# Power_Sheet.net
KiCad netlist of a schematic drawn in Altium Designer
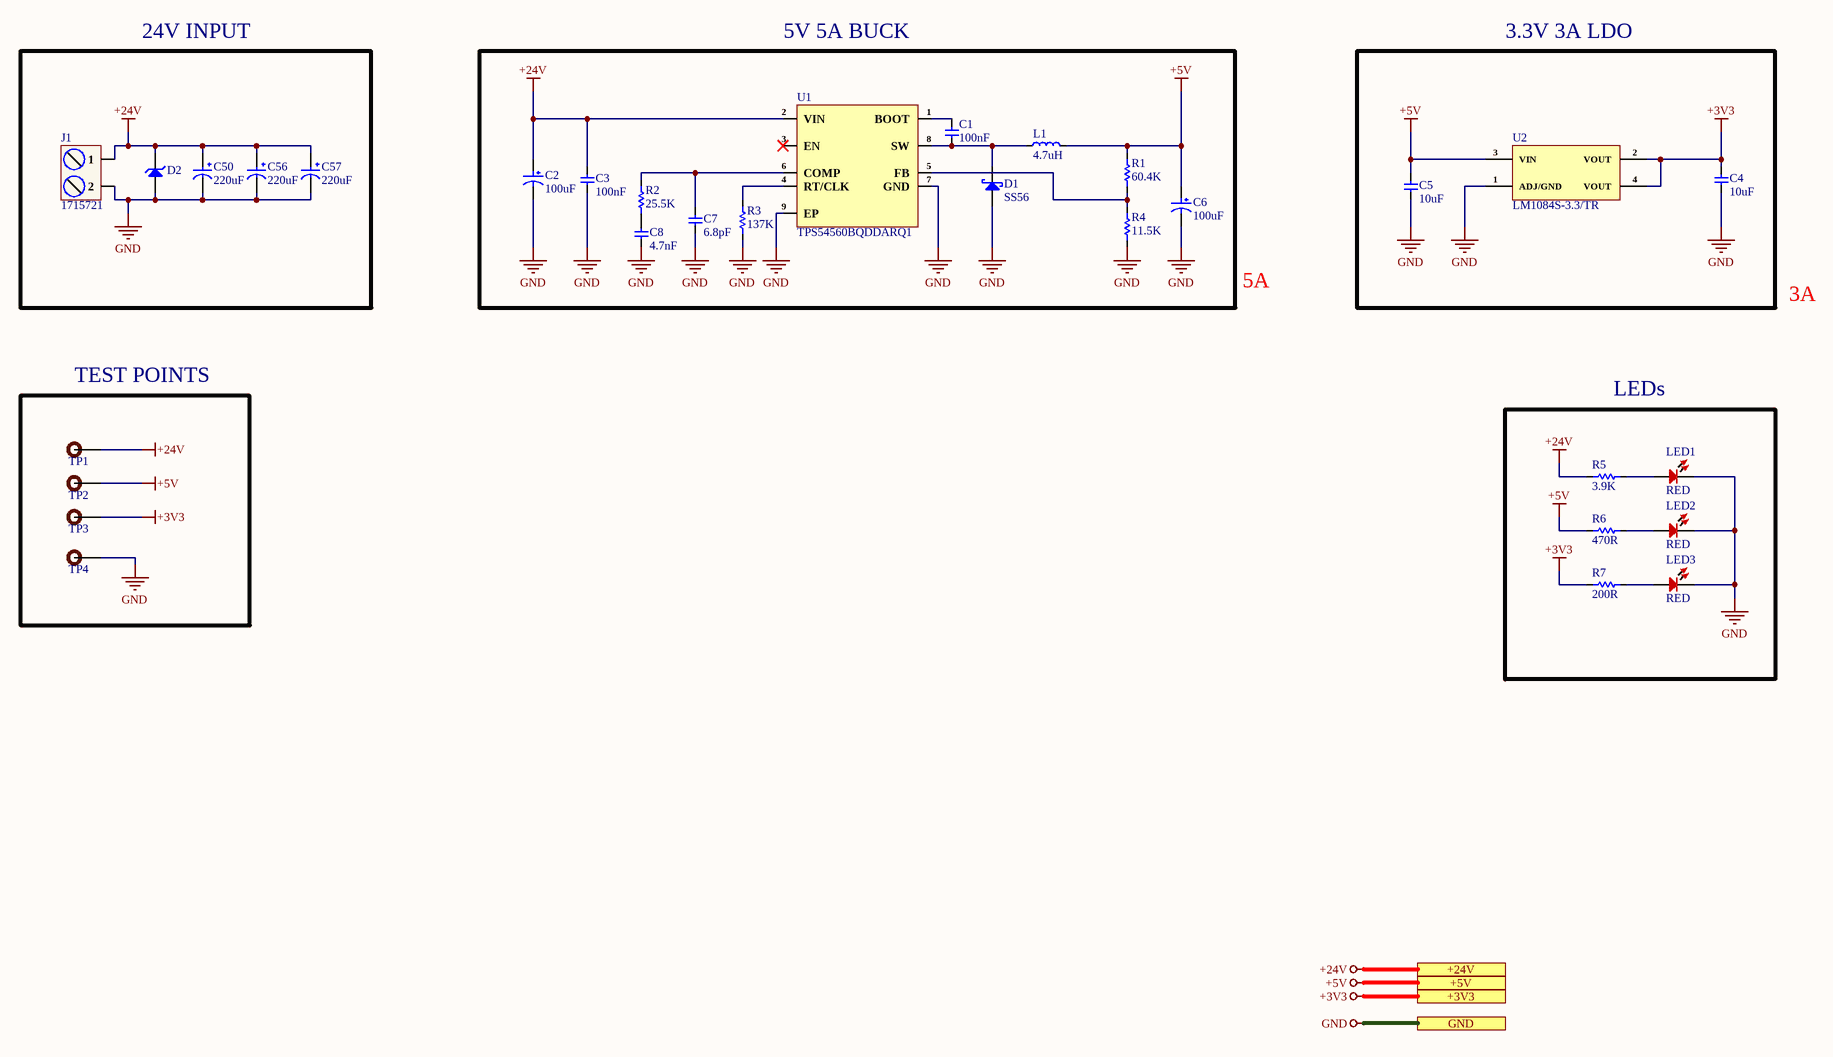
[diagram p0: Power_Sheet.SchDoc]

(export (version "E")
  (design (tool "Eeschema 10.0.6"))
  (components
    (comp (ref "C1")
      (value "100nF")
      (footprint "cap-0402")
      (description "CAP CER 0.1UF 50V X7R 0402")
      (fields
        (field (name "MANUFACTURER") "TDK")
        (field (name "MANUFACTURER PART NUMBER") "C1005X7R1H104KT000F")
      )
      (libsource (lib "eSpark Libraries") (part "C1005X7R1H104KT000F"))
    )
    (comp (ref "C2")
      (value "100uF")
      (footprint "RVT1A101M0605")
      (description "100uF 10V 55mA@120Hz ±20% SMD,D6.3xL5.4mm Aluminum Electrolytic Capacitors - SMD ROHS")
      (fields
        (field (name "MANUFACTURER") "ROQANG")
        (field (name "MANUFACTURER PART NUMBER") "RVT1A101M0605")
      )
      (libsource (lib "eSpark Libraries") (part "RVT1A101M0605"))
    )
    (comp (ref "C3")
      (value "100nF")
      (footprint "cap-0402")
      (description "CAP CER 0.1UF 50V X7R 0402")
      (fields
        (field (name "MANUFACTURER") "TDK")
        (field (name "MANUFACTURER PART NUMBER") "C1005X7R1H104KT000F")
      )
      (libsource (lib "eSpark Libraries") (part "C1005X7R1H104KT000F"))
    )
    (comp (ref "C4")
      (value "10uF")
      (footprint "Cap-0603")
      (description "CAP CER 10UF 25V X5R 0603")
      (fields
        (field (name "MANUFACTURER") "TDK")
        (field (name "MANUFACTURER PART NUMBER") "C1608X5R1E106M080AC")
      )
      (libsource (lib "eSpark Libraries") (part "C1608X5R1E106M080AC"))
    )
    (comp (ref "C5")
      (value "10uF")
      (footprint "Cap-0603")
      (description "CAP CER 10UF 25V X5R 0603")
      (fields
        (field (name "MANUFACTURER") "TDK")
        (field (name "MANUFACTURER PART NUMBER") "C1608X5R1E106M080AC")
      )
      (libsource (lib "eSpark Libraries") (part "C1608X5R1E106M080AC"))
    )
    (comp (ref "C6")
      (value "100uF")
      (footprint "RVT1A101M0605")
      (description "100uF 10V 55mA@120Hz ±20% SMD,D6.3xL5.4mm Aluminum Electrolytic Capacitors - SMD ROHS")
      (fields
        (field (name "MANUFACTURER") "ROQANG")
        (field (name "MANUFACTURER PART NUMBER") "RVT1A101M0605")
      )
      (libsource (lib "eSpark Libraries") (part "RVT1A101M0605"))
    )
    (comp (ref "C7")
      (value "6.8pF")
      (footprint "Cap-0402")
      (description "CAP CER 6.8PF 50V C0G/NPO 0402")
      (fields
        (field (name "MANUFACTURER") "Yageo")
        (field (name "MANUFACTURER PART NUMBER") "CC0402CRNPO9BN6R8")
      )
      (libsource (lib "eSpark Libraries") (part "CC0402CRNPO9BN6R8"))
    )
    (comp (ref "C8")
      (value "4.7nF")
      (footprint "Cap-0402")
      (description "CAP CER 4700PF 50V X7R 0402")
      (fields
        (field (name "MANUFACTURER") "Yageo")
        (field (name "MANUFACTURER PART NUMBER") "CC0402KRX7R9BB472")
      )
      (libsource (lib "eSpark Libraries") (part "CC0402KRX7R9BB472"))
    )
    (comp (ref "C50")
      (value "220uF")
      (footprint "UCD-220uF-10mmDia")
      (description "CAP ALUM 220UF 20% 50V SMD")
      (fields
        (field (name "MANUFACTURER") "Nichicon")
        (field (name "MANUFACTURER PART NUMBER") "UCD1H221MNL1GS")
      )
      (libsource (lib "eSpark Libraries") (part "UCD1H221MNL1GS"))
    )
    (comp (ref "C56")
      (value "220uF")
      (footprint "UCD-220uF-10mmDia")
      (description "CAP ALUM 220UF 20% 50V SMD")
      (fields
        (field (name "MANUFACTURER") "Nichicon")
        (field (name "MANUFACTURER PART NUMBER") "UCD1H221MNL1GS")
      )
      (libsource (lib "eSpark Libraries") (part "UCD1H221MNL1GS"))
    )
    (comp (ref "C57")
      (value "220uF")
      (footprint "UCD-220uF-10mmDia")
      (description "CAP ALUM 220UF 20% 50V SMD")
      (fields
        (field (name "MANUFACTURER") "Nichicon")
        (field (name "MANUFACTURER PART NUMBER") "UCD1H221MNL1GS")
      )
      (libsource (lib "eSpark Libraries") (part "UCD1H221MNL1GS"))
    )
    (comp (ref "D1")
      (value "SS56")
      (footprint "SMA")
      (description "DIODE SCHOTTKY 60V 5A SMA")
      (fields (field (name "MANUFACTURER") "MDD"))
      (libsource (lib "eSpark Libraries") (part "SS56"))
    )
    (comp (ref "D2")
      (value "SMBJ28A-13-F")
      (footprint "SMB_")
      (description "TVS DIODE 28VWM 45.4VC SMB")
      (fields (field (name "MANUFACTURER") "Diodes"))
      (libsource (lib "eSpark Libraries") (part "SMBJ28A-13-F"))
    )
    (comp (ref "J1")
      (value "1715721")
      (footprint "1715721")
      (description "TERM BLK 2P SIDE ENT 5.08MM PCB")
      (fields (field (name "MANUFACTURER") "Phoenix Contact"))
      (libsource (lib "eSpark Libraries") (part "1715721"))
    )
    (comp (ref "L1")
      (value "4.7uH")
      (footprint "YSPI1050-4R7M")
      (description "8A 4.7uH ±20% SMD,10x10.1mm Power Inductors ROHS")
      (fields
        (field (name "MANUFACTURER") "YJYCOIN")
        (field (name "MANUFACTURER PART NUMBER") "YSPI1050-4R7M")
      )
      (libsource (lib "eSpark Libraries") (part "YSPI1050-4R7M"))
    )
    (comp (ref "LED1")
      (value "RED")
      (footprint "LED-0603")
      (description "RED LED 0603 Light Emitting Diodes")
      (fields
        (field (name "MANUFACTURER") "Foshan NationStar Optoelectronics")
        (field (name "MANUFACTURER PART NUMBER") "NCD0603R3")
      )
      (libsource (lib "eSpark Libraries") (part "NCD0603R3"))
    )
    (comp (ref "LED2")
      (value "RED")
      (footprint "LED-0603")
      (description "RED LED 0603 Light Emitting Diodes")
      (fields
        (field (name "MANUFACTURER") "Foshan NationStar Optoelectronics")
        (field (name "MANUFACTURER PART NUMBER") "NCD0603R3")
      )
      (libsource (lib "eSpark Libraries") (part "NCD0603R3"))
    )
    (comp (ref "LED3")
      (value "RED")
      (footprint "LED-0603")
      (description "RED LED 0603 Light Emitting Diodes")
      (fields
        (field (name "MANUFACTURER") "Foshan NationStar Optoelectronics")
        (field (name "MANUFACTURER PART NUMBER") "NCD0603R3")
      )
      (libsource (lib "eSpark Libraries") (part "NCD0603R3"))
    )
    (comp (ref "R1")
      (value "60.4K")
      (footprint "Res-0402")
      (description "60.4kΩ 50V 62.5mW Thick Film Resistors ±1% 0402 Chip Resistor - Surface Mount ROHS")
      (fields (field (name "MANUFACTURER") "VO") (field (name "MANUFACTURER PART NUMBER") "SCR0402F60K4"))
      (libsource (lib "eSpark Libraries") (part "SCR0402F60K4"))
    )
    (comp (ref "R2")
      (value "25.5K")
      (footprint "Res-0402")
      (description "62.5mW Thick Film Resistors 50V ±100ppm/℃ ±1% 25.5kΩ 0402 Chip Resistor - Surface Mount ROHS")
      (fields
        (field (name "LCSC PART NUMBER") "C26970")
        (field (name "MANUFACTURER") "Royal Electronic Factory")
      )
      (libsource (lib "eSpark Libraries") (part "0402WGF2552TCE"))
    )
    (comp (ref "R3")
      (value "137K")
      (footprint "Res-0402")
      (description "RES SMD 137K OHM 0.1% 1/16W 0402")
      (fields (field (name "LCSC PART NUMBER") "C852519") (field (name "MANUFACTURER") "Yageo"))
      (libsource (lib "eSpark Libraries") (part "RT0402BRD07137KL"))
    )
    (comp (ref "R4")
      (value "11.5K")
      (footprint "Res-0402")
      (description "11.5kΩ 50V 62.5mW Thick Film Resistors ±100ppm/℃ ±1%  0402 Chip Resistor - Surface Mount ROHS")
      (fields
        (field (name "MANUFACTURER") "FOJAN")
        (field (name "MANUFACTURER PART NUMBER") "FRC0402F1152TS")
      )
      (libsource (lib "eSpark Libraries") (part "FRC0402F1152TS"))
    )
    (comp (ref "R5")
      (value "3.9K")
      (footprint "Res-0402")
      (description "RES 3.9K OHM 1% 1/16W 0402")
      (fields
        (field (name "MANUFACTURER") "Yageo")
        (field (name "MANUFACTURER PART NUMBER") "RC0402FR-073K9L")
      )
      (libsource (lib "eSpark Libraries") (part "RC0402FR-073K9L"))
    )
    (comp (ref "R6")
      (value "470R")
      (footprint "Res-0402")
      (description "RES 470 OHM 1% 1/16W 0402")
      (fields
        (field (name "MANUFACTURER") "Yageo")
        (field (name "MANUFACTURER PART NUMBER") "RC0402FR-07470RL")
      )
      (libsource (lib "eSpark Libraries") (part "RC0402FR-07470RL"))
    )
    (comp (ref "R7")
      (value "200R")
      (footprint "Res-0402")
      (description "RES 200 OHM 1% 1/16W 0402")
      (fields
        (field (name "MANUFACTURER") "Yageo")
        (field (name "MANUFACTURER PART NUMBER") "RC0402FR-07200RL")
      )
      (libsource (lib "eSpark Libraries") (part "RC0402FR-07200RL"))
    )
    (comp (ref "TP1")
      (value "TEST POINT")
      (footprint "Test-point")
      (description "Test Point ON")
      (libsource (lib "eSpark Libraries") (part "TEST POINT"))
    )
    (comp (ref "TP2")
      (value "TEST POINT")
      (footprint "Test-point")
      (description "Test Point ON")
      (libsource (lib "eSpark Libraries") (part "TEST POINT"))
    )
    (comp (ref "TP3")
      (value "TEST POINT")
      (footprint "Test-point")
      (description "Test Point ON")
      (libsource (lib "eSpark Libraries") (part "TEST POINT"))
    )
    (comp (ref "TP4")
      (value "TEST POINT")
      (footprint "Test-point")
      (description "Test Point ON")
      (libsource (lib "eSpark Libraries") (part "TEST POINT"))
    )
    (comp (ref "U1")
      (value "TPS54560BQDDARQ1")
      (footprint "8-SO PowerPad")
      (description "IC REG BCK SPLIT RAIL ADJ 8SOPWR")
      (fields (field (name "MANUFACTURER") "Texas Instruments") (field (name "LCSC PART NUMBER") "C2072188"))
      (libsource (lib "eSpark Libraries") (part "TPS54560BQDDARQ1"))
    )
    (comp (ref "U2")
      (value "LM1084S-3.3/TR")
      (footprint "TO263-3_")
      (description "72dB@(120Hz) 5A Fixed 3.3V~3.3V Positive 12V TO-263-3 Linear Voltage Regulators (LDO) ROHS")
      (fields (field (name "MANUFACTURER") "HGSEMI") (field (name "LCSC PART NUMBER") "C259972"))
      (libsource (lib "eSpark Libraries") (part "LM1084S-3.3/TR"))
    )
  )
  (nets
    (net (code "1") (name "+3V3") (class "Default")
      (node (ref "C4") (pin "2") (pinfunction "2_2") (pintype "passive"))
      (node (ref "R7") (pin "1") (pinfunction "1_1") (pintype "passive"))
      (node (ref "TP3") (pin "1") (pinfunction "1_1") (pintype "passive"))
      (node (ref "U2") (pin "2") (pinfunction "VOUT_2") (pintype "passive"))
      (node (ref "U2") (pin "4") (pinfunction "VOUT_4") (pintype "passive"))
    )
    (net (code "2") (name "+5V") (class "Default")
      (node (ref "C5") (pin "2") (pinfunction "2_2") (pintype "passive"))
      (node (ref "C6") (pin "1") (pintype "passive"))
      (node (ref "L1") (pin "2") (pinfunction "2_2") (pintype "passive"))
      (node (ref "R1") (pin "2") (pinfunction "2_2") (pintype "passive"))
      (node (ref "R6") (pin "1") (pinfunction "1_1") (pintype "passive"))
      (node (ref "TP2") (pin "1") (pinfunction "1_1") (pintype "passive"))
      (node (ref "U2") (pin "3") (pinfunction "VIN_3") (pintype "passive"))
    )
    (net (code "3") (name "+24V") (class "Default")
      (node (ref "C2") (pin "1") (pintype "passive"))
      (node (ref "C3") (pin "2") (pinfunction "2_2") (pintype "passive"))
      (node (ref "C50") (pin "1") (pinfunction "1_1") (pintype "passive"))
      (node (ref "C56") (pin "1") (pinfunction "1_1") (pintype "passive"))
      (node (ref "C57") (pin "1") (pinfunction "1_1") (pintype "passive"))
      (node (ref "D2") (pin "2") (pinfunction "K_2") (pintype "passive"))
      (node (ref "J1") (pin "1") (pinfunction "1_1") (pintype "passive"))
      (node (ref "R5") (pin "1") (pinfunction "1_1") (pintype "passive"))
      (node (ref "TP1") (pin "1") (pinfunction "1_1") (pintype "passive"))
      (node (ref "U1") (pin "2") (pinfunction "VIN_2") (pintype "passive"))
    )
    (net (code "4") (name "GND") (class "Default")
      (node (ref "C2") (pin "2") (pintype "passive"))
      (node (ref "C3") (pin "1") (pinfunction "1_1") (pintype "passive"))
      (node (ref "C4") (pin "1") (pinfunction "1_1") (pintype "passive"))
      (node (ref "C5") (pin "1") (pinfunction "1_1") (pintype "passive"))
      (node (ref "C50") (pin "2") (pinfunction "2_2") (pintype "passive"))
      (node (ref "C56") (pin "2") (pinfunction "2_2") (pintype "passive"))
      (node (ref "C57") (pin "2") (pinfunction "2_2") (pintype "passive"))
      (node (ref "C6") (pin "2") (pintype "passive"))
      (node (ref "C7") (pin "1") (pinfunction "1_1") (pintype "passive"))
      (node (ref "C8") (pin "1") (pinfunction "1_1") (pintype "passive"))
      (node (ref "D1") (pin "2") (pinfunction "A_2") (pintype "passive"))
      (node (ref "D2") (pin "1") (pinfunction "A_1") (pintype "passive"))
      (node (ref "J1") (pin "2") (pinfunction "2_2") (pintype "passive"))
      (node (ref "LED1") (pin "2") (pinfunction "2_2") (pintype "passive"))
      (node (ref "LED2") (pin "2") (pinfunction "2_2") (pintype "passive"))
      (node (ref "LED3") (pin "2") (pinfunction "2_2") (pintype "passive"))
      (node (ref "R3") (pin "1") (pinfunction "1_1") (pintype "passive"))
      (node (ref "R4") (pin "1") (pinfunction "1_1") (pintype "passive"))
      (node (ref "TP4") (pin "1") (pinfunction "1_1") (pintype "passive"))
      (node (ref "U1") (pin "7") (pinfunction "GND_7") (pintype "passive"))
      (node (ref "U1") (pin "9") (pinfunction "EP_9") (pintype "passive"))
      (node (ref "U2") (pin "1") (pinfunction "ADJ/GND_1") (pintype "passive"))
    )
    (net (code "5") (name "Net-(C8-Pad2)") (class "Default")
      (node (ref "C8") (pin "2") (pinfunction "2_2") (pintype "passive"))
      (node (ref "R2") (pin "1") (pinfunction "1_1") (pintype "passive"))
    )
    (net (code "6") (name "Net-(D1-K)") (class "Default")
      (node (ref "C1") (pin "1") (pinfunction "1_1") (pintype "passive"))
      (node (ref "D1") (pin "1") (pinfunction "K_1") (pintype "passive"))
      (node (ref "L1") (pin "1") (pinfunction "1_1") (pintype "passive"))
      (node (ref "U1") (pin "8") (pinfunction "SW_8") (pintype "passive"))
    )
    (net (code "7") (name "Net-(LED1-Pad1)") (class "Default")
      (node (ref "LED1") (pin "1") (pinfunction "1_1") (pintype "passive"))
      (node (ref "R5") (pin "2") (pinfunction "2_2") (pintype "passive"))
    )
    (net (code "8") (name "Net-(LED2-Pad1)") (class "Default")
      (node (ref "LED2") (pin "1") (pinfunction "1_1") (pintype "passive"))
      (node (ref "R6") (pin "2") (pinfunction "2_2") (pintype "passive"))
    )
    (net (code "9") (name "Net-(LED3-Pad1)") (class "Default")
      (node (ref "LED3") (pin "1") (pinfunction "1_1") (pintype "passive"))
      (node (ref "R7") (pin "2") (pinfunction "2_2") (pintype "passive"))
    )
    (net (code "10") (name "Net-(U1-BOOT)") (class "Default")
      (node (ref "C1") (pin "2") (pinfunction "2_2") (pintype "passive"))
      (node (ref "U1") (pin "1") (pinfunction "BOOT_1") (pintype "passive"))
    )
    (net (code "11") (name "Net-(U1-COMP)") (class "Default")
      (node (ref "C7") (pin "2") (pinfunction "2_2") (pintype "passive"))
      (node (ref "R2") (pin "2") (pinfunction "2_2") (pintype "passive"))
      (node (ref "U1") (pin "6") (pinfunction "COMP_6") (pintype "passive"))
    )
    (net (code "12") (name "Net-(U1-FB)") (class "Default")
      (node (ref "R1") (pin "1") (pinfunction "1_1") (pintype "passive"))
      (node (ref "R4") (pin "2") (pinfunction "2_2") (pintype "passive"))
      (node (ref "U1") (pin "5") (pinfunction "FB_5") (pintype "passive"))
    )
    (net (code "13") (name "Net-(U1-RT{slash}CLK)") (class "Default")
      (node (ref "R3") (pin "2") (pinfunction "2_2") (pintype "passive"))
      (node (ref "U1") (pin "4") (pinfunction "RT/CLK_4") (pintype "passive"))
    )
    (net (code "14") (name "unconnected-(U1-EN-Pad3)") (class "Default")
      (node (ref "U1") (pin "3") (pinfunction "EN_3") (pintype "passive+no_connect"))
    )
  )
)
